# apds9250.net
KiCad netlist of a schematic drawn in EAGLE
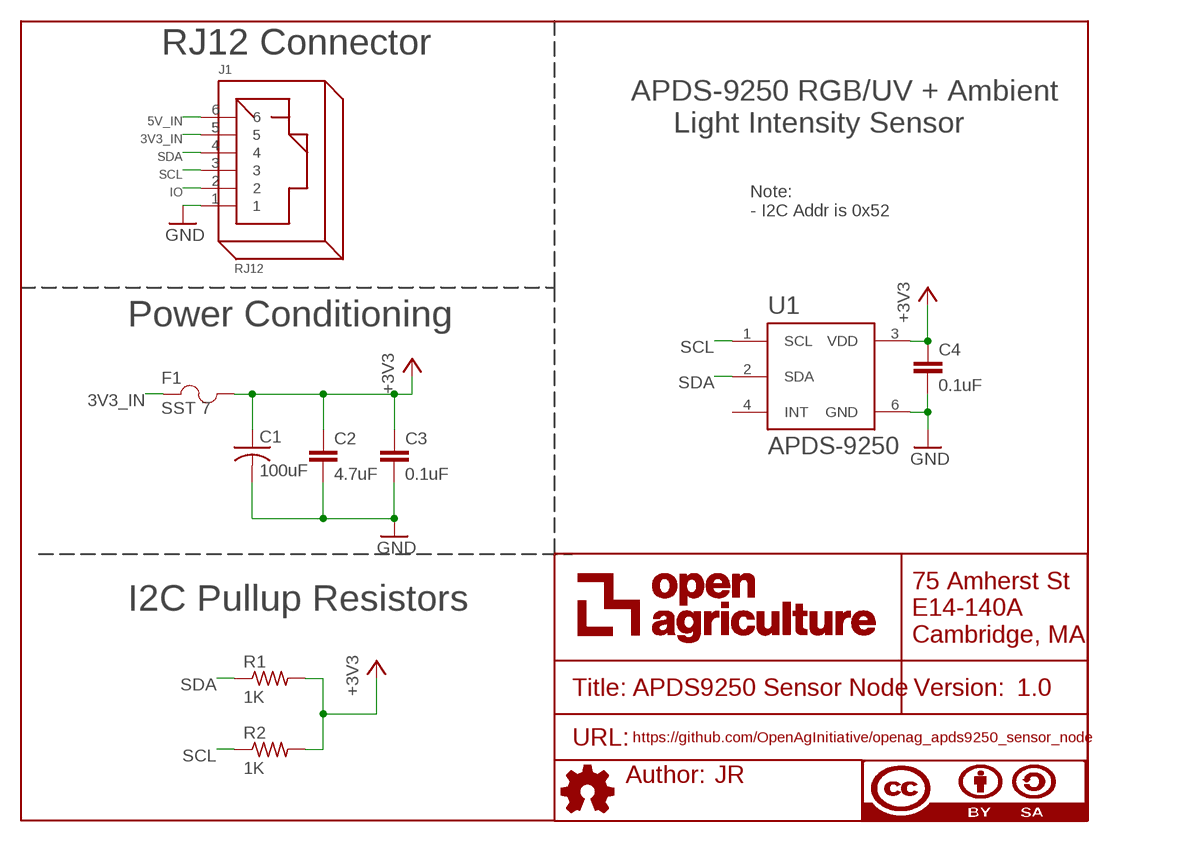
[diagram p0: schematic, sheet 1]

(export (version "E")
  (design (tool "Eeschema 10.0.6"))
  (components
    (comp (ref "C1")
      (value "100uF")
      (footprint "eagle-import:EEE-1HA101UP")
      (libsource (lib "eagle-import") (part "100UF-EEE-1HA101UP"))
    )
    (comp (ref "C2")
      (value "4.7uF")
      (footprint "eagle-import:C0805")
      (libsource (lib "eagle-import") (part "4.7UF-CL21A475KBQNNNE"))
    )
    (comp (ref "C3")
      (value "0.1uF")
      (footprint "eagle-import:C0603")
      (libsource (lib "eagle-import") (part "0.1UF-C0603C104K5RACTU"))
    )
    (comp (ref "C4")
      (value "0.1uF")
      (footprint "eagle-import:C0603")
      (libsource (lib "eagle-import") (part "0.1UF-C0603C104K5RACTU"))
    )
    (comp (ref "F1")
      (value "SST 7")
      (footprint "eagle-import:SS")
      (libsource (lib "eagle-import") (part "SST_7"))
    )
    (comp (ref "FRAME1")
      (value "DOCFIELD")
      (footprint "eagle-import:DOCFIELD")
      (description "APDS-9250 RGB/UV + Ambient Light Intensity Sensor Node")
      (fields
        (field (name "TITLE") "Example Template")
        (field (name "AUTHOR") "XX")
        (field (name "VER") "1.0")
        (field (name "URL") "https://github.com/OpenAgInitiative/openag_eagle_template")
        (field (name "AUTHOR_1") "JR")
        (field (name "TITLE_1") "APDS9250 Sensor Node")
        (field (name "URL_1") "https://github.com/OpenAgInitiative/openag_apds9250_sensor_node")
      )
      (libsource (lib "eagle-import") (part "DOCFIELD"))
    )
    (comp (ref "J1")
      (value "RJ12")
      (footprint "eagle-import:RJ12")
      (libsource (lib "eagle-import") (part "A-2004-1-4-LP-N-R"))
    )
    (comp (ref "R1")
      (value "1K")
      (footprint "eagle-import:RC0603N")
      (libsource (lib "eagle-import") (part "1K-ERJ-PB3D1001V"))
    )
    (comp (ref "R2")
      (value "1K")
      (footprint "eagle-import:RC0603N")
      (libsource (lib "eagle-import") (part "1K-ERJ-PB3D1001V"))
    )
    (comp (ref "U1")
      (value "APDS-9250")
      (footprint "eagle-import:APDS-9250")
      (libsource (lib "eagle-import") (part "APDS-9250"))
    )
  )
  (nets
    (net (code "1") (name "+3V3") (class "Default")
      (node (ref "C1") (pin "+") (pinfunction "1(+)_+") (pintype "passive"))
      (node (ref "C2") (pin "1") (pinfunction "1_1") (pintype "passive"))
      (node (ref "C3") (pin "1") (pinfunction "1_1") (pintype "passive"))
      (node (ref "C4") (pin "1") (pinfunction "1_1") (pintype "passive"))
      (node (ref "F1") (pin "2") (pinfunction "2_2") (pintype "passive"))
      (node (ref "R1") (pin "2") (pinfunction "2_2") (pintype "passive"))
      (node (ref "R2") (pin "2") (pinfunction "2_2") (pintype "passive"))
      (node (ref "U1") (pin "3") (pinfunction "VDD_3") (pintype "power_in"))
    )
    (net (code "2") (name "3V3_IN") (class "Default")
      (node (ref "F1") (pin "1") (pinfunction "1_1") (pintype "passive"))
      (node (ref "J1") (pin "5") (pinfunction "5_5") (pintype "bidirectional"))
    )
    (net (code "3") (name "5V_IN") (class "Default")
      (node (ref "J1") (pin "6") (pinfunction "6_6") (pintype "bidirectional"))
    )
    (net (code "4") (name "GND") (class "Default")
      (node (ref "C1") (pin "-") (pinfunction "2(-)_-") (pintype "passive"))
      (node (ref "C2") (pin "2") (pinfunction "2_2") (pintype "passive"))
      (node (ref "C3") (pin "2") (pinfunction "2_2") (pintype "passive"))
      (node (ref "C4") (pin "2") (pinfunction "2_2") (pintype "passive"))
      (node (ref "J1") (pin "1") (pinfunction "1_1") (pintype "bidirectional"))
      (node (ref "U1") (pin "6") (pinfunction "GND_6") (pintype "power_in"))
    )
    (net (code "5") (name "IO") (class "Default")
      (node (ref "J1") (pin "2") (pinfunction "2_2") (pintype "bidirectional"))
    )
    (net (code "6") (name "SCL") (class "Default")
      (node (ref "J1") (pin "3") (pinfunction "3_3") (pintype "bidirectional"))
      (node (ref "R2") (pin "1") (pinfunction "1_1") (pintype "passive"))
      (node (ref "U1") (pin "1") (pinfunction "SCL_1") (pintype "bidirectional"))
    )
    (net (code "7") (name "SDA") (class "Default")
      (node (ref "J1") (pin "4") (pinfunction "4_4") (pintype "bidirectional"))
      (node (ref "R1") (pin "1") (pinfunction "1_1") (pintype "passive"))
      (node (ref "U1") (pin "2") (pinfunction "SDA_2") (pintype "bidirectional"))
    )
    (net (code "8") (name "unconnected-(U1-INT-Pad4)") (class "Default")
      (node (ref "U1") (pin "4") (pinfunction "INT_4") (pintype "bidirectional"))
    )
  )
)
